# QuadPower.net
KiCad netlist of a schematic drawn in EasyEDA Pro
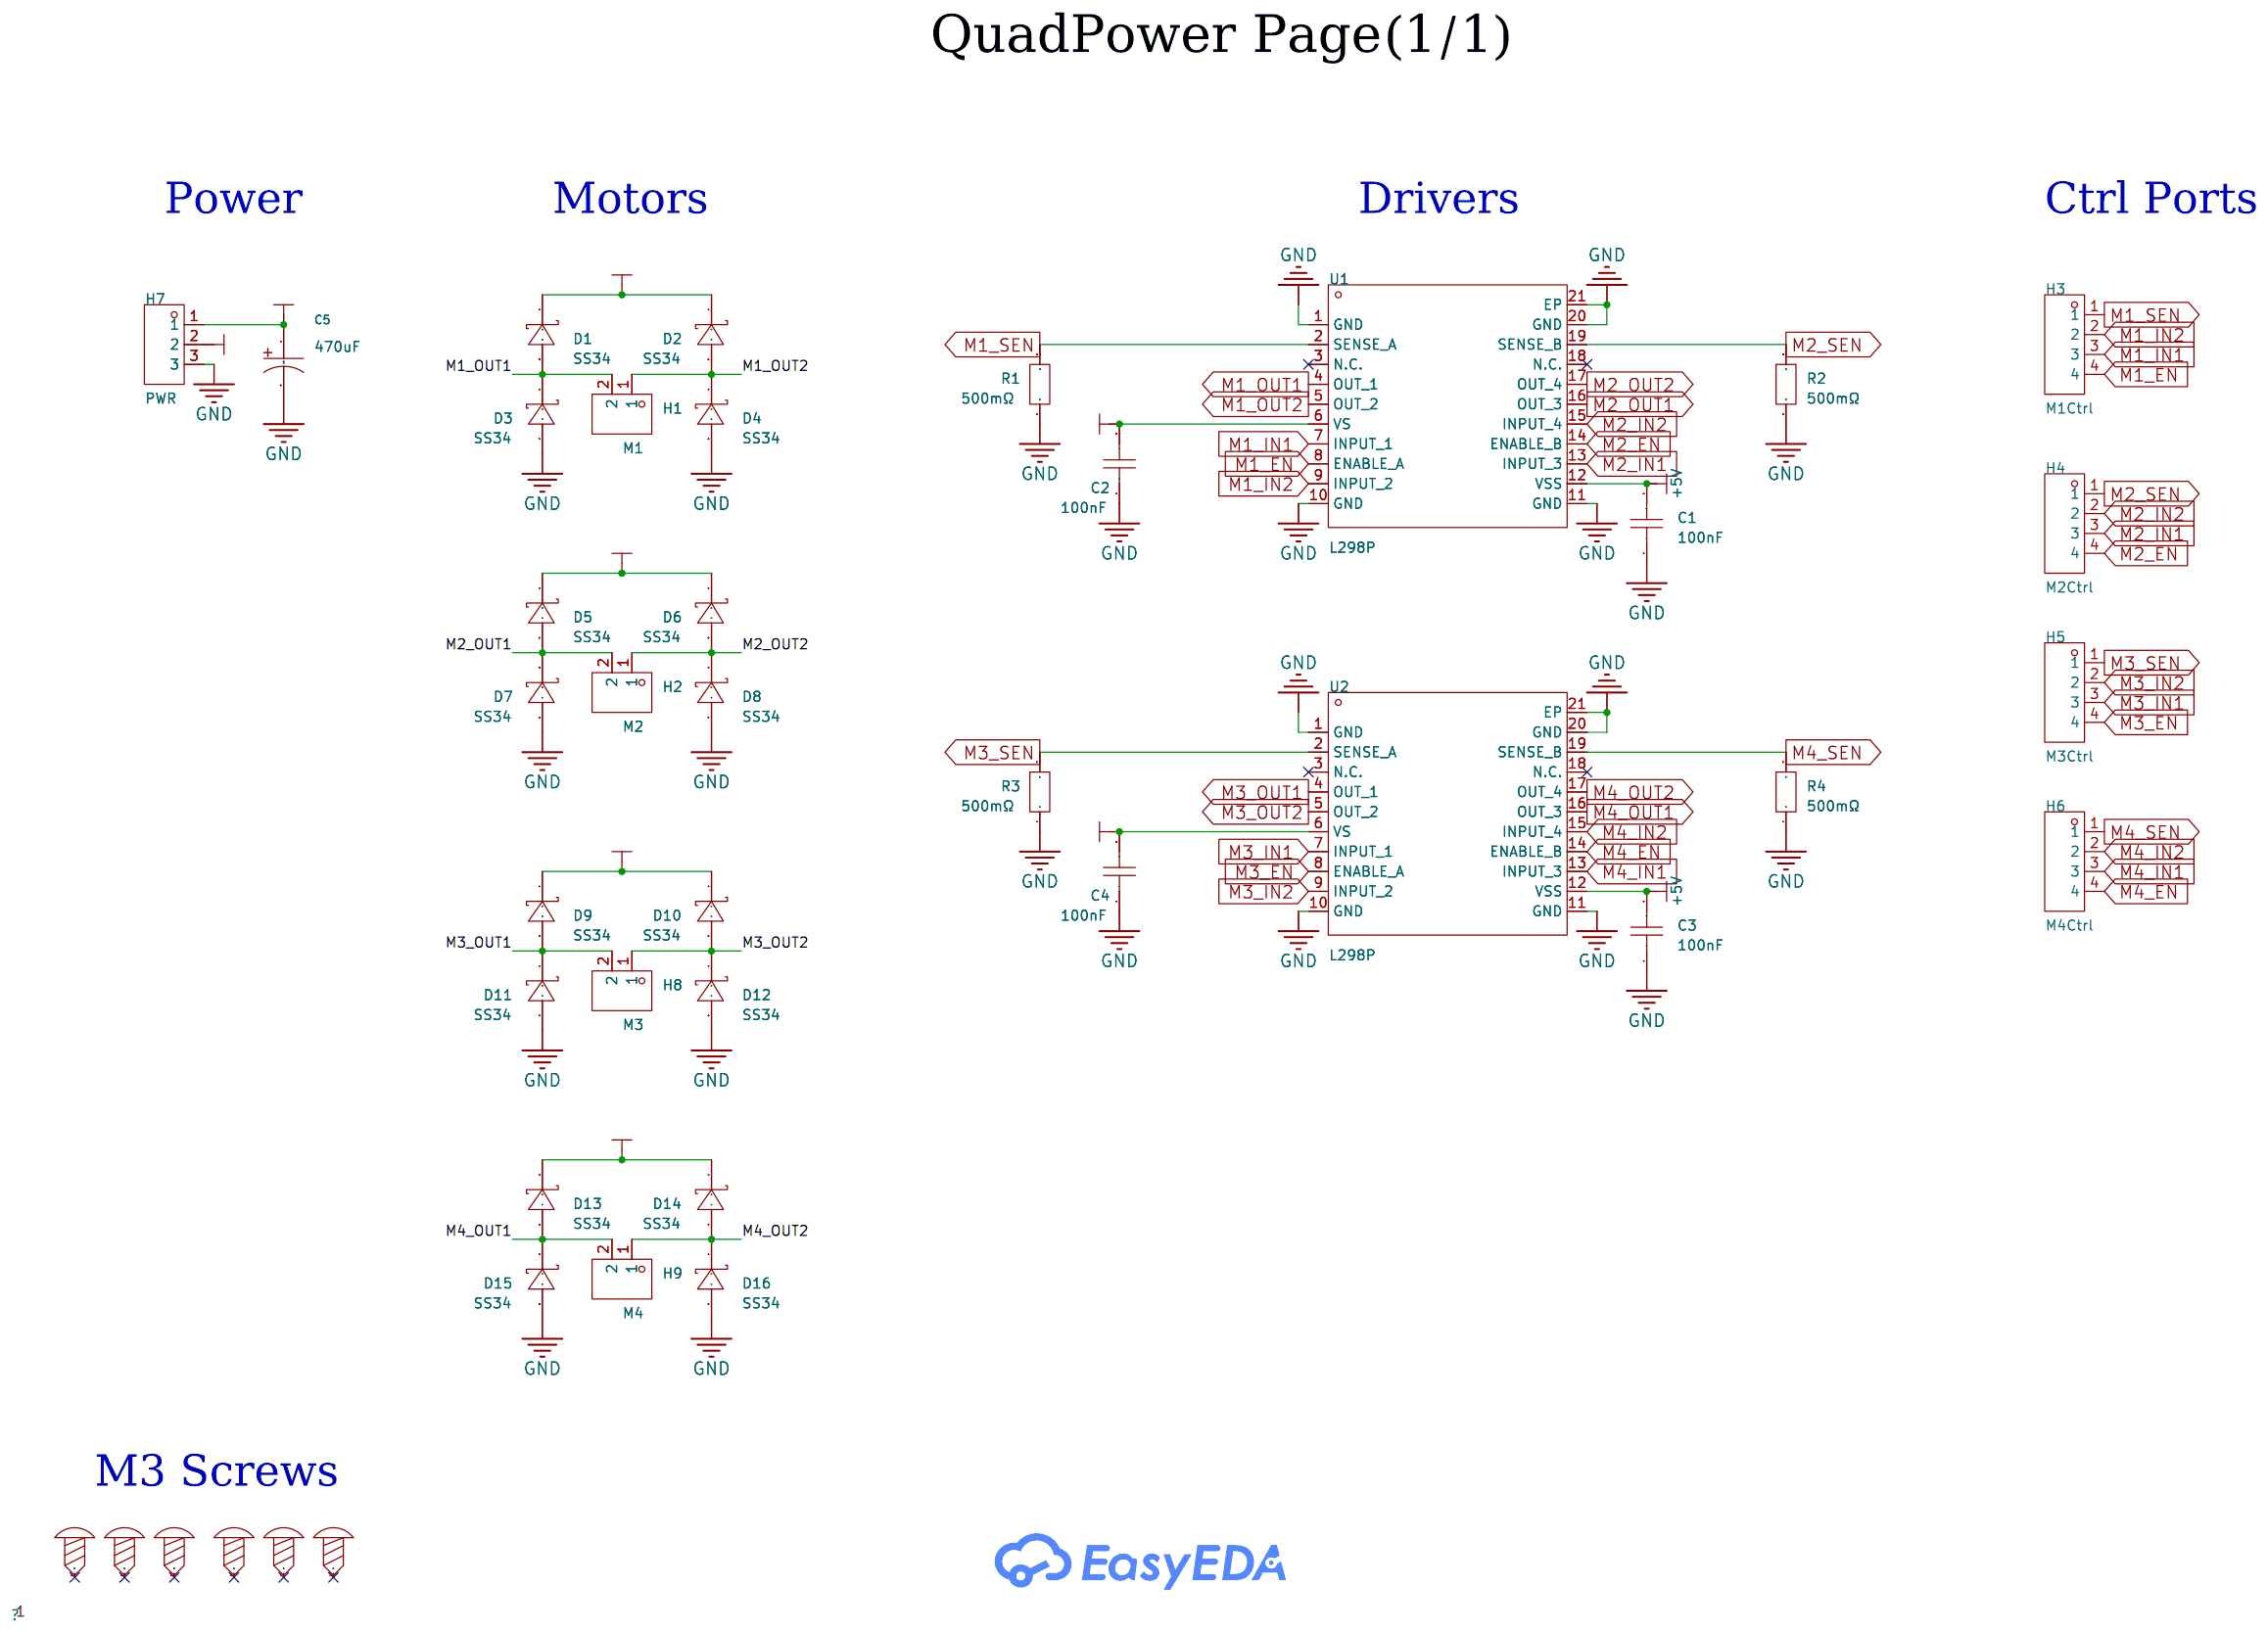
[diagram p0: schematic sheet]

(export (version "E")
  (design (tool "Eeschema 10.0.6"))
  (components
    (comp (ref "C1")
      (value "100nF")
      (footprint "easyedapro:C0603")
      (fields
        (field (name "Manufacturer Part") "CGA0603X7R104K500JT")
        (field (name "Manufacturer") "HRE(芯声)")
      )
      (libsource (lib "easyedapro") (part "CGA0603X7R104K500JT"))
    )
    (comp (ref "C2")
      (value "100nF")
      (footprint "easyedapro:C0603")
      (fields
        (field (name "Manufacturer Part") "CGA0603X7R104K500JT")
        (field (name "Manufacturer") "HRE(芯声)")
      )
      (libsource (lib "easyedapro") (part "CGA0603X7R104K500JT"))
    )
    (comp (ref "C3")
      (value "100nF")
      (footprint "easyedapro:C0603")
      (fields
        (field (name "Manufacturer Part") "CGA0603X7R104K500JT")
        (field (name "Manufacturer") "HRE(芯声)")
      )
      (libsource (lib "easyedapro") (part "CGA0603X7R104K500JT"))
    )
    (comp (ref "C4")
      (value "100nF")
      (footprint "easyedapro:C0603")
      (fields
        (field (name "Manufacturer Part") "CGA0603X7R104K500JT")
        (field (name "Manufacturer") "HRE(芯声)")
      )
      (libsource (lib "easyedapro") (part "CGA0603X7R104K500JT"))
    )
    (comp (ref "C5")
      (value "470uF")
      (footprint "easyedapro:CAP-SMD_BD10.0-L10.3-W10.3-FD")
      (fields
        (field (name "Manufacturer Part") "RVT470UF50V34RV0133")
        (field (name "Manufacturer") "KNSCHA(科尼盛)")
      )
      (libsource (lib "easyedapro") (part "EEHZS1V471P"))
    )
    (comp (ref "D1")
      (value "SS34")
      (footprint "easyedapro:SMA_L4.3-W2.6-LS5.2-RD")
      (fields (field (name "Manufacturer") "MDD(辰达半导体)"))
      (libsource (lib "easyedapro") (part "SS34_C8678"))
    )
    (comp (ref "D2")
      (value "SS34")
      (footprint "easyedapro:SMA_L4.3-W2.6-LS5.2-RD")
      (fields (field (name "Manufacturer") "MDD(辰达半导体)"))
      (libsource (lib "easyedapro") (part "SS34_C8678"))
    )
    (comp (ref "D3")
      (value "SS34")
      (footprint "easyedapro:SMA_L4.3-W2.6-LS5.2-RD")
      (fields (field (name "Manufacturer") "MDD(辰达半导体)"))
      (libsource (lib "easyedapro") (part "SS34_C8678"))
    )
    (comp (ref "D4")
      (value "SS34")
      (footprint "easyedapro:SMA_L4.3-W2.6-LS5.2-RD")
      (fields (field (name "Manufacturer") "MDD(辰达半导体)"))
      (libsource (lib "easyedapro") (part "SS34_C8678"))
    )
    (comp (ref "D5")
      (value "SS34")
      (footprint "easyedapro:SMA_L4.3-W2.6-LS5.2-RD")
      (fields (field (name "Manufacturer") "MDD(辰达半导体)"))
      (libsource (lib "easyedapro") (part "SS34_C8678"))
    )
    (comp (ref "D6")
      (value "SS34")
      (footprint "easyedapro:SMA_L4.3-W2.6-LS5.2-RD")
      (fields (field (name "Manufacturer") "MDD(辰达半导体)"))
      (libsource (lib "easyedapro") (part "SS34_C8678"))
    )
    (comp (ref "D7")
      (value "SS34")
      (footprint "easyedapro:SMA_L4.3-W2.6-LS5.2-RD")
      (fields (field (name "Manufacturer") "MDD(辰达半导体)"))
      (libsource (lib "easyedapro") (part "SS34_C8678"))
    )
    (comp (ref "D8")
      (value "SS34")
      (footprint "easyedapro:SMA_L4.3-W2.6-LS5.2-RD")
      (fields (field (name "Manufacturer") "MDD(辰达半导体)"))
      (libsource (lib "easyedapro") (part "SS34_C8678"))
    )
    (comp (ref "D9")
      (value "SS34")
      (footprint "easyedapro:SMA_L4.3-W2.6-LS5.2-RD")
      (fields (field (name "Manufacturer") "MDD(辰达半导体)"))
      (libsource (lib "easyedapro") (part "SS34_C8678"))
    )
    (comp (ref "D10")
      (value "SS34")
      (footprint "easyedapro:SMA_L4.3-W2.6-LS5.2-RD")
      (fields (field (name "Manufacturer") "MDD(辰达半导体)"))
      (libsource (lib "easyedapro") (part "SS34_C8678"))
    )
    (comp (ref "D11")
      (value "SS34")
      (footprint "easyedapro:SMA_L4.3-W2.6-LS5.2-RD")
      (fields (field (name "Manufacturer") "MDD(辰达半导体)"))
      (libsource (lib "easyedapro") (part "SS34_C8678"))
    )
    (comp (ref "D12")
      (value "SS34")
      (footprint "easyedapro:SMA_L4.3-W2.6-LS5.2-RD")
      (fields (field (name "Manufacturer") "MDD(辰达半导体)"))
      (libsource (lib "easyedapro") (part "SS34_C8678"))
    )
    (comp (ref "D13")
      (value "SS34")
      (footprint "easyedapro:SMA_L4.3-W2.6-LS5.2-RD")
      (fields (field (name "Manufacturer") "MDD(辰达半导体)"))
      (libsource (lib "easyedapro") (part "SS34_C8678"))
    )
    (comp (ref "D14")
      (value "SS34")
      (footprint "easyedapro:SMA_L4.3-W2.6-LS5.2-RD")
      (fields (field (name "Manufacturer") "MDD(辰达半导体)"))
      (libsource (lib "easyedapro") (part "SS34_C8678"))
    )
    (comp (ref "D15")
      (value "SS34")
      (footprint "easyedapro:SMA_L4.3-W2.6-LS5.2-RD")
      (fields (field (name "Manufacturer") "MDD(辰达半导体)"))
      (libsource (lib "easyedapro") (part "SS34_C8678"))
    )
    (comp (ref "D16")
      (value "SS34")
      (footprint "easyedapro:SMA_L4.3-W2.6-LS5.2-RD")
      (fields (field (name "Manufacturer") "MDD(辰达半导体)"))
      (libsource (lib "easyedapro") (part "SS34_C8678"))
    )
    (comp (ref "H1")
      (value "M1")
      (footprint "easyedapro:CONN-TH_DB301V-3.5-2P-GN")
      (fields
        (field (name "Manufacturer Part") "DB125-3.81-2P-GN-S")
        (field (name "Manufacturer") "DORABO(地博电气)")
      )
      (libsource (lib "easyedapro") (part "DB301V-3.5-2P-GN"))
    )
    (comp (ref "H2")
      (value "M2")
      (footprint "easyedapro:CONN-TH_DB301V-3.5-2P-GN")
      (fields
        (field (name "Manufacturer Part") "DB125-3.81-2P-GN-S")
        (field (name "Manufacturer") "DORABO(地博电气)")
      )
      (libsource (lib "easyedapro") (part "DB301V-3.5-2P-GN"))
    )
    (comp (ref "H3")
      (value "M1Ctrl")
      (footprint "easyedapro:CONN-TH_DB125-2.54-4P-GN")
      (fields
        (field (name "Manufacturer Part") "DB125-2.54-4P-GN-S")
        (field (name "Manufacturer") "DORABO(地博电气)")
      )
      (libsource (lib "easyedapro") (part "DB125-2.54-4P-GN"))
    )
    (comp (ref "H4")
      (value "M2Ctrl")
      (footprint "easyedapro:CONN-TH_DB125-2.54-4P-GN")
      (fields
        (field (name "Manufacturer Part") "DB125-2.54-4P-GN-S")
        (field (name "Manufacturer") "DORABO(地博电气)")
      )
      (libsource (lib "easyedapro") (part "DB125-2.54-4P-GN"))
    )
    (comp (ref "H5")
      (value "M3Ctrl")
      (footprint "easyedapro:CONN-TH_DB125-2.54-4P-GN")
      (fields
        (field (name "Manufacturer Part") "DB125-2.54-4P-GN-S")
        (field (name "Manufacturer") "DORABO(地博电气)")
      )
      (libsource (lib "easyedapro") (part "DB125-2.54-4P-GN"))
    )
    (comp (ref "H6")
      (value "M4Ctrl")
      (footprint "easyedapro:CONN-TH_DB125-2.54-4P-GN")
      (fields
        (field (name "Manufacturer Part") "DB125-2.54-4P-GN-S")
        (field (name "Manufacturer") "DORABO(地博电气)")
      )
      (libsource (lib "easyedapro") (part "DB125-2.54-4P-GN"))
    )
    (comp (ref "H7")
      (value "PWR")
      (footprint "easyedapro:CONN-TH_DB301V-3.5-3P-GN")
      (fields
        (field (name "Manufacturer Part") "DB125-3.81-3P-GN-S")
        (field (name "Manufacturer") "DORABO(地博电气)")
      )
      (libsource (lib "easyedapro") (part "DB301V-3.5-3P-GN"))
    )
    (comp (ref "H8")
      (value "M3")
      (footprint "easyedapro:CONN-TH_DB301V-3.5-2P-GN")
      (fields
        (field (name "Manufacturer Part") "DB125-3.81-2P-GN-S")
        (field (name "Manufacturer") "DORABO(地博电气)")
      )
      (libsource (lib "easyedapro") (part "DB301V-3.5-2P-GN"))
    )
    (comp (ref "H9")
      (value "M4")
      (footprint "easyedapro:CONN-TH_DB301V-3.5-2P-GN")
      (fields
        (field (name "Manufacturer Part") "DB125-3.81-2P-GN-S")
        (field (name "Manufacturer") "DORABO(地博电气)")
      )
      (libsource (lib "easyedapro") (part "DB301V-3.5-2P-GN"))
    )
    (comp (ref "R1")
      (value "500mΩ")
      (footprint "easyedapro:R1206")
      (fields
        (field (name "Manufacturer Part") "HoYH1206-1W-500mR-1%")
        (field (name "Manufacturer") "Milliohm(毫欧)")
      )
      (libsource (lib "easyedapro") (part "HOYH1206-1W-500MR-1%"))
    )
    (comp (ref "R2")
      (value "500mΩ")
      (footprint "easyedapro:R1206")
      (fields
        (field (name "Manufacturer Part") "HoYH1206-1W-500mR-1%")
        (field (name "Manufacturer") "Milliohm(毫欧)")
      )
      (libsource (lib "easyedapro") (part "HOYH1206-1W-500MR-1%"))
    )
    (comp (ref "R3")
      (value "500mΩ")
      (footprint "easyedapro:R1206")
      (fields
        (field (name "Manufacturer Part") "HoYH1206-1W-500mR-1%")
        (field (name "Manufacturer") "Milliohm(毫欧)")
      )
      (libsource (lib "easyedapro") (part "HOYH1206-1W-500MR-1%"))
    )
    (comp (ref "R4")
      (value "500mΩ")
      (footprint "easyedapro:R1206")
      (fields
        (field (name "Manufacturer Part") "HoYH1206-1W-500mR-1%")
        (field (name "Manufacturer") "Milliohm(毫欧)")
      )
      (libsource (lib "easyedapro") (part "HOYH1206-1W-500MR-1%"))
    )
    (comp (ref "SCREW1")
      (value "~")
      (footprint "easyedapro:Screw-Hole-M3")
      (libsource (lib "easyedapro") (part "Screw-Hole"))
    )
    (comp (ref "SCREW2")
      (value "~")
      (footprint "easyedapro:Screw-Hole-M3")
      (libsource (lib "easyedapro") (part "Screw-Hole"))
    )
    (comp (ref "SCREW3")
      (value "~")
      (footprint "easyedapro:Screw-Hole-M3")
      (libsource (lib "easyedapro") (part "Screw-Hole"))
    )
    (comp (ref "SCREW4")
      (value "~")
      (footprint "easyedapro:Screw-Hole-M3")
      (libsource (lib "easyedapro") (part "Screw-Hole"))
    )
    (comp (ref "SCREW5")
      (value "~")
      (footprint "easyedapro:Screw-Hole-M3")
      (libsource (lib "easyedapro") (part "Screw-Hole"))
    )
    (comp (ref "SCREW6")
      (value "~")
      (footprint "easyedapro:Screw-Hole-M3")
      (libsource (lib "easyedapro") (part "Screw-Hole"))
    )
    (comp (ref "U1")
      (value "L298P")
      (footprint "easyedapro:POWERSO20_L15.9-W11.0-P1.27-LS14.2-BL-EP")
      (fields (field (name "Manufacturer") "ST(意法半导体)"))
      (libsource (lib "easyedapro") (part "L298P"))
    )
    (comp (ref "U2")
      (value "L298P")
      (footprint "easyedapro:POWERSO20_L15.9-W11.0-P1.27-LS14.2-BL-EP")
      (fields (field (name "Manufacturer") "ST(意法半导体)"))
      (libsource (lib "easyedapro") (part "L298P"))
    )
  )
  (nets
    (net (code "1") (name "+5V") (class "Default")
      (node (ref "C1") (pin "2") (pinfunction "2_2") (pintype "unspecified"))
      (node (ref "C3") (pin "2") (pinfunction "2_2") (pintype "unspecified"))
      (node (ref "H7") (pin "2") (pinfunction "2_2") (pintype "unspecified"))
      (node (ref "U1") (pin "12") (pinfunction "VSS_12") (pintype "unspecified"))
      (node (ref "U2") (pin "12") (pinfunction "VSS_12") (pintype "unspecified"))
    )
    (net (code "2") (name "GND") (class "Default")
      (node (ref "C1") (pin "1") (pinfunction "1_1") (pintype "unspecified"))
      (node (ref "C2") (pin "1") (pinfunction "1_1") (pintype "unspecified"))
      (node (ref "C3") (pin "1") (pinfunction "1_1") (pintype "unspecified"))
      (node (ref "C4") (pin "1") (pinfunction "1_1") (pintype "unspecified"))
      (node (ref "C5") (pin "2") (pinfunction "2_2") (pintype "input"))
      (node (ref "D11") (pin "2") (pinfunction "A_2") (pintype "unspecified"))
      (node (ref "D12") (pin "2") (pinfunction "A_2") (pintype "unspecified"))
      (node (ref "D15") (pin "2") (pinfunction "A_2") (pintype "unspecified"))
      (node (ref "D16") (pin "2") (pinfunction "A_2") (pintype "unspecified"))
      (node (ref "D3") (pin "2") (pinfunction "A_2") (pintype "unspecified"))
      (node (ref "D4") (pin "2") (pinfunction "A_2") (pintype "unspecified"))
      (node (ref "D7") (pin "2") (pinfunction "A_2") (pintype "unspecified"))
      (node (ref "D8") (pin "2") (pinfunction "A_2") (pintype "unspecified"))
      (node (ref "H7") (pin "3") (pinfunction "3_3") (pintype "unspecified"))
      (node (ref "R1") (pin "1") (pinfunction "1_1") (pintype "unspecified"))
      (node (ref "R2") (pin "1") (pinfunction "1_1") (pintype "unspecified"))
      (node (ref "R3") (pin "1") (pinfunction "1_1") (pintype "unspecified"))
      (node (ref "R4") (pin "1") (pinfunction "1_1") (pintype "unspecified"))
      (node (ref "U1") (pin "1") (pinfunction "GND_1") (pintype "unspecified"))
      (node (ref "U1") (pin "10") (pinfunction "GND_10") (pintype "unspecified"))
      (node (ref "U1") (pin "11") (pinfunction "GND_11") (pintype "unspecified"))
      (node (ref "U1") (pin "20") (pinfunction "GND_20") (pintype "unspecified"))
      (node (ref "U1") (pin "21") (pinfunction "EP_21") (pintype "unspecified"))
      (node (ref "U2") (pin "1") (pinfunction "GND_1") (pintype "unspecified"))
      (node (ref "U2") (pin "10") (pinfunction "GND_10") (pintype "unspecified"))
      (node (ref "U2") (pin "11") (pinfunction "GND_11") (pintype "unspecified"))
      (node (ref "U2") (pin "20") (pinfunction "GND_20") (pintype "unspecified"))
      (node (ref "U2") (pin "21") (pinfunction "EP_21") (pintype "unspecified"))
    )
    (net (code "3") (name "M1_EN") (class "Default")
      (node (ref "H3") (pin "4") (pinfunction "4_4") (pintype "unspecified"))
      (node (ref "U1") (pin "8") (pinfunction "ENABLE_A_8") (pintype "unspecified"))
    )
    (net (code "4") (name "M1_IN1") (class "Default")
      (node (ref "H3") (pin "3") (pinfunction "3_3") (pintype "unspecified"))
      (node (ref "U1") (pin "7") (pinfunction "INPUT_1_7") (pintype "unspecified"))
    )
    (net (code "5") (name "M1_IN2") (class "Default")
      (node (ref "H3") (pin "2") (pinfunction "2_2") (pintype "unspecified"))
      (node (ref "U1") (pin "9") (pinfunction "INPUT_2_9") (pintype "unspecified"))
    )
    (net (code "6") (name "M1_OUT1") (class "Default")
      (node (ref "D1") (pin "2") (pinfunction "A_2") (pintype "unspecified"))
      (node (ref "D3") (pin "1") (pinfunction "K_1") (pintype "unspecified"))
      (node (ref "H1") (pin "2") (pinfunction "2_2") (pintype "unspecified"))
      (node (ref "U1") (pin "4") (pinfunction "OUT_1_4") (pintype "unspecified"))
    )
    (net (code "7") (name "M1_OUT2") (class "Default")
      (node (ref "D2") (pin "2") (pinfunction "A_2") (pintype "unspecified"))
      (node (ref "D4") (pin "1") (pinfunction "K_1") (pintype "unspecified"))
      (node (ref "H1") (pin "1") (pinfunction "1_1") (pintype "unspecified"))
      (node (ref "U1") (pin "5") (pinfunction "OUT_2_5") (pintype "unspecified"))
    )
    (net (code "8") (name "M1_SEN") (class "Default")
      (node (ref "H3") (pin "1") (pinfunction "1_1") (pintype "unspecified"))
      (node (ref "R1") (pin "2") (pinfunction "2_2") (pintype "unspecified"))
      (node (ref "U1") (pin "2") (pinfunction "SENSE_A_2") (pintype "unspecified"))
    )
    (net (code "9") (name "M2_EN") (class "Default")
      (node (ref "H4") (pin "4") (pinfunction "4_4") (pintype "unspecified"))
      (node (ref "U1") (pin "14") (pinfunction "ENABLE_B_14") (pintype "unspecified"))
    )
    (net (code "10") (name "M2_IN1") (class "Default")
      (node (ref "H4") (pin "3") (pinfunction "3_3") (pintype "unspecified"))
      (node (ref "U1") (pin "13") (pinfunction "INPUT_3_13") (pintype "unspecified"))
    )
    (net (code "11") (name "M2_IN2") (class "Default")
      (node (ref "H4") (pin "2") (pinfunction "2_2") (pintype "unspecified"))
      (node (ref "U1") (pin "15") (pinfunction "INPUT_4_15") (pintype "unspecified"))
    )
    (net (code "12") (name "M2_OUT1") (class "Default")
      (node (ref "D5") (pin "2") (pinfunction "A_2") (pintype "unspecified"))
      (node (ref "D7") (pin "1") (pinfunction "K_1") (pintype "unspecified"))
      (node (ref "H2") (pin "2") (pinfunction "2_2") (pintype "unspecified"))
      (node (ref "U1") (pin "16") (pinfunction "OUT_3_16") (pintype "unspecified"))
    )
    (net (code "13") (name "M2_OUT2") (class "Default")
      (node (ref "D6") (pin "2") (pinfunction "A_2") (pintype "unspecified"))
      (node (ref "D8") (pin "1") (pinfunction "K_1") (pintype "unspecified"))
      (node (ref "H2") (pin "1") (pinfunction "1_1") (pintype "unspecified"))
      (node (ref "U1") (pin "17") (pinfunction "OUT_4_17") (pintype "unspecified"))
    )
    (net (code "14") (name "M2_SEN") (class "Default")
      (node (ref "H4") (pin "1") (pinfunction "1_1") (pintype "unspecified"))
      (node (ref "R2") (pin "2") (pinfunction "2_2") (pintype "unspecified"))
      (node (ref "U1") (pin "19") (pinfunction "SENSE_B_19") (pintype "unspecified"))
    )
    (net (code "15") (name "M3_EN") (class "Default")
      (node (ref "H5") (pin "4") (pinfunction "4_4") (pintype "unspecified"))
      (node (ref "U2") (pin "8") (pinfunction "ENABLE_A_8") (pintype "unspecified"))
    )
    (net (code "16") (name "M3_IN1") (class "Default")
      (node (ref "H5") (pin "3") (pinfunction "3_3") (pintype "unspecified"))
      (node (ref "U2") (pin "7") (pinfunction "INPUT_1_7") (pintype "unspecified"))
    )
    (net (code "17") (name "M3_IN2") (class "Default")
      (node (ref "H5") (pin "2") (pinfunction "2_2") (pintype "unspecified"))
      (node (ref "U2") (pin "9") (pinfunction "INPUT_2_9") (pintype "unspecified"))
    )
    (net (code "18") (name "M3_OUT1") (class "Default")
      (node (ref "D11") (pin "1") (pinfunction "K_1") (pintype "unspecified"))
      (node (ref "D9") (pin "2") (pinfunction "A_2") (pintype "unspecified"))
      (node (ref "H8") (pin "2") (pinfunction "2_2") (pintype "unspecified"))
      (node (ref "U2") (pin "4") (pinfunction "OUT_1_4") (pintype "unspecified"))
    )
    (net (code "19") (name "M3_OUT2") (class "Default")
      (node (ref "D10") (pin "2") (pinfunction "A_2") (pintype "unspecified"))
      (node (ref "D12") (pin "1") (pinfunction "K_1") (pintype "unspecified"))
      (node (ref "H8") (pin "1") (pinfunction "1_1") (pintype "unspecified"))
      (node (ref "U2") (pin "5") (pinfunction "OUT_2_5") (pintype "unspecified"))
    )
    (net (code "20") (name "M3_SEN") (class "Default")
      (node (ref "H5") (pin "1") (pinfunction "1_1") (pintype "unspecified"))
      (node (ref "R3") (pin "2") (pinfunction "2_2") (pintype "unspecified"))
      (node (ref "U2") (pin "2") (pinfunction "SENSE_A_2") (pintype "unspecified"))
    )
    (net (code "21") (name "M4_EN") (class "Default")
      (node (ref "H6") (pin "4") (pinfunction "4_4") (pintype "unspecified"))
      (node (ref "U2") (pin "14") (pinfunction "ENABLE_B_14") (pintype "unspecified"))
    )
    (net (code "22") (name "M4_IN1") (class "Default")
      (node (ref "H6") (pin "3") (pinfunction "3_3") (pintype "unspecified"))
      (node (ref "U2") (pin "13") (pinfunction "INPUT_3_13") (pintype "unspecified"))
    )
    (net (code "23") (name "M4_IN2") (class "Default")
      (node (ref "H6") (pin "2") (pinfunction "2_2") (pintype "unspecified"))
      (node (ref "U2") (pin "15") (pinfunction "INPUT_4_15") (pintype "unspecified"))
    )
    (net (code "24") (name "M4_OUT1") (class "Default")
      (node (ref "D13") (pin "2") (pinfunction "A_2") (pintype "unspecified"))
      (node (ref "D15") (pin "1") (pinfunction "K_1") (pintype "unspecified"))
      (node (ref "H9") (pin "2") (pinfunction "2_2") (pintype "unspecified"))
      (node (ref "U2") (pin "16") (pinfunction "OUT_3_16") (pintype "unspecified"))
    )
    (net (code "25") (name "M4_OUT2") (class "Default")
      (node (ref "D14") (pin "2") (pinfunction "A_2") (pintype "unspecified"))
      (node (ref "D16") (pin "1") (pinfunction "K_1") (pintype "unspecified"))
      (node (ref "H9") (pin "1") (pinfunction "1_1") (pintype "unspecified"))
      (node (ref "U2") (pin "17") (pinfunction "OUT_4_17") (pintype "unspecified"))
    )
    (net (code "26") (name "M4_SEN") (class "Default")
      (node (ref "H6") (pin "1") (pinfunction "1_1") (pintype "unspecified"))
      (node (ref "R4") (pin "2") (pinfunction "2_2") (pintype "unspecified"))
      (node (ref "U2") (pin "19") (pinfunction "SENSE_B_19") (pintype "unspecified"))
    )
    (net (code "27") (name "VS") (class "Default")
      (node (ref "C2") (pin "2") (pinfunction "2_2") (pintype "unspecified"))
      (node (ref "C4") (pin "2") (pinfunction "2_2") (pintype "unspecified"))
      (node (ref "C5") (pin "1") (pinfunction "1_1") (pintype "input"))
      (node (ref "D1") (pin "1") (pinfunction "K_1") (pintype "unspecified"))
      (node (ref "D10") (pin "1") (pinfunction "K_1") (pintype "unspecified"))
      (node (ref "D13") (pin "1") (pinfunction "K_1") (pintype "unspecified"))
      (node (ref "D14") (pin "1") (pinfunction "K_1") (pintype "unspecified"))
      (node (ref "D2") (pin "1") (pinfunction "K_1") (pintype "unspecified"))
      (node (ref "D5") (pin "1") (pinfunction "K_1") (pintype "unspecified"))
      (node (ref "D6") (pin "1") (pinfunction "K_1") (pintype "unspecified"))
      (node (ref "D9") (pin "1") (pinfunction "K_1") (pintype "unspecified"))
      (node (ref "H7") (pin "1") (pinfunction "1_1") (pintype "unspecified"))
      (node (ref "U1") (pin "6") (pinfunction "VS_6") (pintype "unspecified"))
      (node (ref "U2") (pin "6") (pinfunction "VS_6") (pintype "unspecified"))
    )
    (net (code "28") (name "unconnected-(SCREW1-Pad1)") (class "Default")
      (node (ref "SCREW1") (pin "1") (pinfunction "1_1") (pintype "input+no_connect"))
    )
    (net (code "29") (name "unconnected-(SCREW2-Pad1)") (class "Default")
      (node (ref "SCREW2") (pin "1") (pinfunction "1_1") (pintype "input+no_connect"))
    )
    (net (code "30") (name "unconnected-(SCREW3-Pad1)") (class "Default")
      (node (ref "SCREW3") (pin "1") (pinfunction "1_1") (pintype "input+no_connect"))
    )
    (net (code "31") (name "unconnected-(SCREW4-Pad1)") (class "Default")
      (node (ref "SCREW4") (pin "1") (pinfunction "1_1") (pintype "input+no_connect"))
    )
    (net (code "32") (name "unconnected-(SCREW5-Pad1)") (class "Default")
      (node (ref "SCREW5") (pin "1") (pinfunction "1_1") (pintype "input+no_connect"))
    )
    (net (code "33") (name "unconnected-(SCREW6-Pad1)") (class "Default")
      (node (ref "SCREW6") (pin "1") (pinfunction "1_1") (pintype "input+no_connect"))
    )
    (net (code "34") (name "unconnected-(U1-N.C.-Pad3)") (class "Default")
      (node (ref "U1") (pin "3") (pinfunction "N.C._3") (pintype "unspecified+no_connect"))
    )
    (net (code "35") (name "unconnected-(U1-N.C.-Pad18)") (class "Default")
      (node (ref "U1") (pin "18") (pinfunction "N.C._18") (pintype "unspecified+no_connect"))
    )
    (net (code "36") (name "unconnected-(U2-N.C.-Pad3)") (class "Default")
      (node (ref "U2") (pin "3") (pinfunction "N.C._3") (pintype "unspecified+no_connect"))
    )
    (net (code "37") (name "unconnected-(U2-N.C.-Pad18)") (class "Default")
      (node (ref "U2") (pin "18") (pinfunction "N.C._18") (pintype "unspecified+no_connect"))
    )
  )
)
